# SmartCubeExtension.net
KiCad netlist of a schematic drawn in Altium Designer
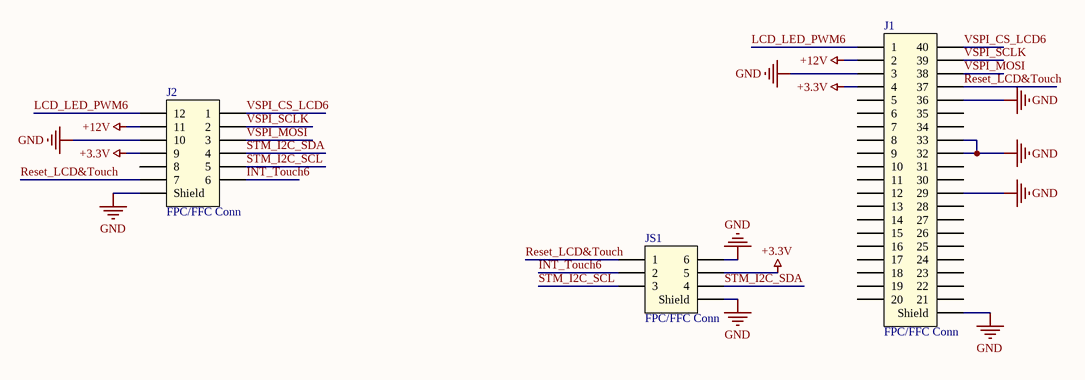
[diagram p0: SmartCubeExtension.SchDoc]

(export (version "E")
  (design (tool "Eeschema 10.0.6"))
  (components
    (comp (ref "J1")
      (value "FPC/FFC Conn")
      (footprint "FH12-40S Vertical")
      (description "Connector to Display's trail")
      (fields
        (field (name "PART NUMBER") "FH12-40S-0.5SVA(54)")
        (field (name "MANUFACTURER") "Hirose Electric")
      )
      (libsource (lib "Karen_Components") (part "Conn40x1 (FH12 Vertical)"))
    )
    (comp (ref "J2")
      (value "FPC/FFC Conn")
      (footprint "FH12-12S Vertical")
      (description "Connector to trail")
      (fields
        (field (name "PART NUMBER") "FH12-12S-0.5SVA(54)")
        (field (name "MANUFACTURER") "Hirose Electric")
      )
      (libsource (lib "Karen_Components") (part "Conn12x1 (FH12 Vertical)"))
    )
    (comp (ref "JS1")
      (value "FPC/FFC Conn")
      (footprint "FH12-6s Vertical")
      (description "Connector to touch sensor's trail")
      (fields
        (field (name "PART NUMBER") "FH12-6S-0.5SVA(54)")
        (field (name "MANUFACTURER") "Hirose Electric")
      )
      (libsource (lib "Karen_Components") (part "Conn6x1 (FH12 Vertical)"))
    )
  )
  (nets
    (net (code "1") (name "+3.3V") (class "Default")
      (node (ref "J1") (pin "4") (pinfunction "4_4") (pintype "passive"))
      (node (ref "J2") (pin "9") (pinfunction "9_9") (pintype "passive"))
      (node (ref "JS1") (pin "5") (pinfunction "5_5") (pintype "passive"))
    )
    (net (code "2") (name "+12V") (class "Default")
      (node (ref "J1") (pin "2") (pinfunction "2_2") (pintype "passive"))
      (node (ref "J2") (pin "11") (pinfunction "11_11") (pintype "passive"))
    )
    (net (code "3") (name "/INT_Touch6") (class "Default")
      (node (ref "J2") (pin "6") (pinfunction "6_6") (pintype "passive"))
      (node (ref "JS1") (pin "2") (pinfunction "2_2") (pintype "passive"))
    )
    (net (code "4") (name "/LCD_LED_PWM6") (class "Default")
      (node (ref "J1") (pin "1") (pinfunction "1_1") (pintype "passive"))
      (node (ref "J2") (pin "12") (pinfunction "12_12") (pintype "passive"))
    )
    (net (code "5") (name "/Reset_LCD&Touch") (class "Default")
      (node (ref "J1") (pin "37") (pinfunction "37_37") (pintype "passive"))
      (node (ref "J2") (pin "7") (pinfunction "7_7") (pintype "passive"))
      (node (ref "JS1") (pin "1") (pinfunction "1_1") (pintype "passive"))
    )
    (net (code "6") (name "/STM_I2C_SCL") (class "Default")
      (node (ref "J2") (pin "5") (pinfunction "5_5") (pintype "passive"))
      (node (ref "JS1") (pin "3") (pinfunction "3_3") (pintype "passive"))
    )
    (net (code "7") (name "/STM_I2C_SDA") (class "Default")
      (node (ref "J2") (pin "4") (pinfunction "4_4") (pintype "passive"))
      (node (ref "JS1") (pin "4") (pinfunction "4_4") (pintype "passive"))
    )
    (net (code "8") (name "/VSPI_CS_LCD6") (class "Default")
      (node (ref "J1") (pin "40") (pinfunction "40_40") (pintype "passive"))
      (node (ref "J2") (pin "1") (pinfunction "1_1") (pintype "passive"))
    )
    (net (code "9") (name "/VSPI_MOSI") (class "Default")
      (node (ref "J1") (pin "38") (pinfunction "38_38") (pintype "passive"))
      (node (ref "J2") (pin "3") (pinfunction "3_3") (pintype "passive"))
    )
    (net (code "10") (name "/VSPI_SCLK") (class "Default")
      (node (ref "J1") (pin "39") (pinfunction "39_39") (pintype "passive"))
      (node (ref "J2") (pin "2") (pinfunction "2_2") (pintype "passive"))
    )
    (net (code "11") (name "GND") (class "Default")
      (node (ref "J1") (pin "29") (pinfunction "29_29") (pintype "passive"))
      (node (ref "J1") (pin "3") (pinfunction "3_3") (pintype "passive"))
      (node (ref "J1") (pin "32") (pinfunction "32_32") (pintype "passive"))
      (node (ref "J1") (pin "33") (pinfunction "33_33") (pintype "passive"))
      (node (ref "J1") (pin "36") (pinfunction "36_36") (pintype "passive"))
      (node (ref "J1") (pin "A") (pinfunction "Shield_A") (pintype "passive"))
      (node (ref "J2") (pin "10") (pinfunction "10_10") (pintype "passive"))
      (node (ref "J2") (pin "A") (pinfunction "Shield_A") (pintype "passive"))
      (node (ref "JS1") (pin "6") (pinfunction "6_6") (pintype "passive"))
      (node (ref "JS1") (pin "A") (pinfunction "Shield_A") (pintype "passive"))
    )
    (net (code "12") (name "unconnected-(J1-Pad5)") (class "Default")
      (node (ref "J1") (pin "5") (pinfunction "5_5") (pintype "passive"))
    )
    (net (code "13") (name "unconnected-(J1-Pad6)") (class "Default")
      (node (ref "J1") (pin "6") (pinfunction "6_6") (pintype "passive"))
    )
    (net (code "14") (name "unconnected-(J1-Pad7)") (class "Default")
      (node (ref "J1") (pin "7") (pinfunction "7_7") (pintype "passive"))
    )
    (net (code "15") (name "unconnected-(J1-Pad8)") (class "Default")
      (node (ref "J1") (pin "8") (pinfunction "8_8") (pintype "passive"))
    )
    (net (code "16") (name "unconnected-(J1-Pad9)") (class "Default")
      (node (ref "J1") (pin "9") (pinfunction "9_9") (pintype "passive"))
    )
    (net (code "17") (name "unconnected-(J1-Pad10)") (class "Default")
      (node (ref "J1") (pin "10") (pinfunction "10_10") (pintype "passive"))
    )
    (net (code "18") (name "unconnected-(J1-Pad11)") (class "Default")
      (node (ref "J1") (pin "11") (pinfunction "11_11") (pintype "passive"))
    )
    (net (code "19") (name "unconnected-(J1-Pad12)") (class "Default")
      (node (ref "J1") (pin "12") (pinfunction "12_12") (pintype "passive"))
    )
    (net (code "20") (name "unconnected-(J1-Pad13)") (class "Default")
      (node (ref "J1") (pin "13") (pinfunction "13_13") (pintype "passive"))
    )
    (net (code "21") (name "unconnected-(J1-Pad14)") (class "Default")
      (node (ref "J1") (pin "14") (pinfunction "14_14") (pintype "passive"))
    )
    (net (code "22") (name "unconnected-(J1-Pad15)") (class "Default")
      (node (ref "J1") (pin "15") (pinfunction "15_15") (pintype "passive"))
    )
    (net (code "23") (name "unconnected-(J1-Pad16)") (class "Default")
      (node (ref "J1") (pin "16") (pinfunction "16_16") (pintype "passive"))
    )
    (net (code "24") (name "unconnected-(J1-Pad17)") (class "Default")
      (node (ref "J1") (pin "17") (pinfunction "17_17") (pintype "passive"))
    )
    (net (code "25") (name "unconnected-(J1-Pad18)") (class "Default")
      (node (ref "J1") (pin "18") (pinfunction "18_18") (pintype "passive"))
    )
    (net (code "26") (name "unconnected-(J1-Pad19)") (class "Default")
      (node (ref "J1") (pin "19") (pinfunction "19_19") (pintype "passive"))
    )
    (net (code "27") (name "unconnected-(J1-Pad20)") (class "Default")
      (node (ref "J1") (pin "20") (pinfunction "20_20") (pintype "passive"))
    )
    (net (code "28") (name "unconnected-(J1-Pad21)") (class "Default")
      (node (ref "J1") (pin "21") (pinfunction "21_21") (pintype "passive"))
    )
    (net (code "29") (name "unconnected-(J1-Pad22)") (class "Default")
      (node (ref "J1") (pin "22") (pinfunction "22_22") (pintype "passive"))
    )
    (net (code "30") (name "unconnected-(J1-Pad23)") (class "Default")
      (node (ref "J1") (pin "23") (pinfunction "23_23") (pintype "passive"))
    )
    (net (code "31") (name "unconnected-(J1-Pad24)") (class "Default")
      (node (ref "J1") (pin "24") (pinfunction "24_24") (pintype "passive"))
    )
    (net (code "32") (name "unconnected-(J1-Pad25)") (class "Default")
      (node (ref "J1") (pin "25") (pinfunction "25_25") (pintype "passive"))
    )
    (net (code "33") (name "unconnected-(J1-Pad26)") (class "Default")
      (node (ref "J1") (pin "26") (pinfunction "26_26") (pintype "passive"))
    )
    (net (code "34") (name "unconnected-(J1-Pad27)") (class "Default")
      (node (ref "J1") (pin "27") (pinfunction "27_27") (pintype "passive"))
    )
    (net (code "35") (name "unconnected-(J1-Pad28)") (class "Default")
      (node (ref "J1") (pin "28") (pinfunction "28_28") (pintype "passive"))
    )
    (net (code "36") (name "unconnected-(J1-Pad30)") (class "Default")
      (node (ref "J1") (pin "30") (pinfunction "30_30") (pintype "passive"))
    )
    (net (code "37") (name "unconnected-(J1-Pad31)") (class "Default")
      (node (ref "J1") (pin "31") (pinfunction "31_31") (pintype "passive"))
    )
    (net (code "38") (name "unconnected-(J1-Pad34)") (class "Default")
      (node (ref "J1") (pin "34") (pinfunction "34_34") (pintype "passive"))
    )
    (net (code "39") (name "unconnected-(J1-Pad35)") (class "Default")
      (node (ref "J1") (pin "35") (pinfunction "35_35") (pintype "passive"))
    )
    (net (code "40") (name "unconnected-(J2-Pad8)") (class "Default")
      (node (ref "J2") (pin "8") (pinfunction "8_8") (pintype "passive"))
    )
  )
)
